# USB_to_UART.net
KiCad netlist of a schematic drawn in Altium Designer
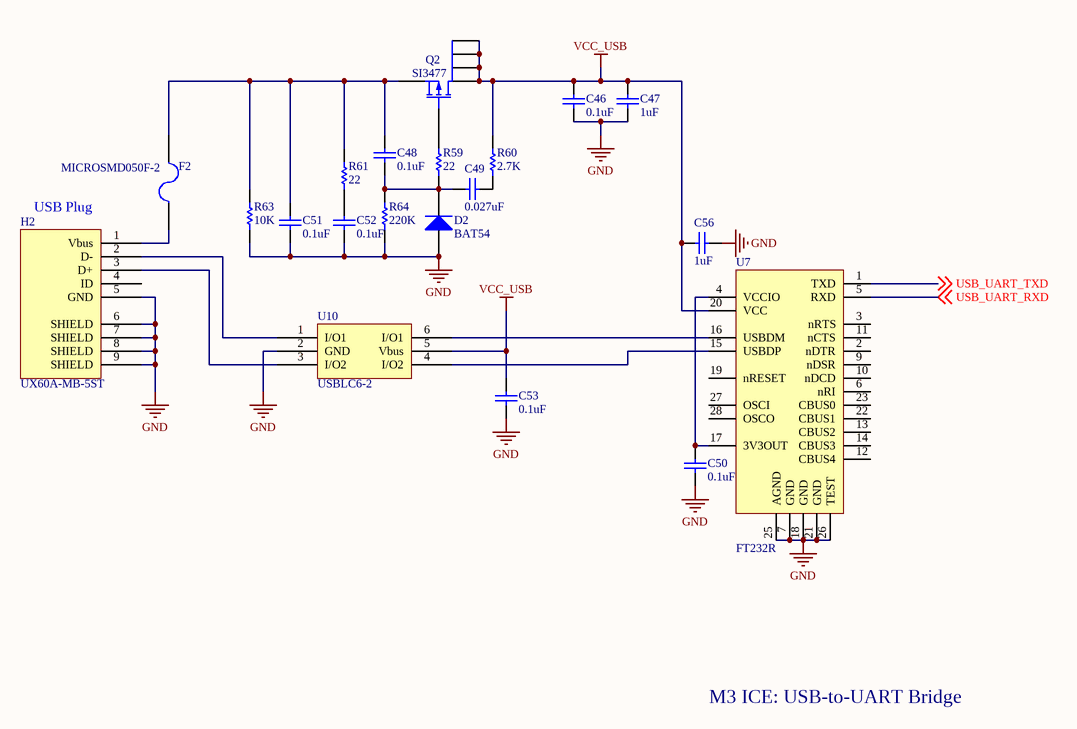
[diagram p0: USB_to_UART.SchDoc]

(export (version "E")
  (design (tool "Eeschema 10.0.6"))
  (components
    (comp (ref "C46")
      (value "0.1uF")
      (footprint "1608[0603]")
      (description "Capacitor (Semiconductor SIM Model)")
      (fields
        (field (name "DISTPARTNO") "1276-1005-1-ND")
        (field (name "MANPARTNO") "CL10B104KO8NNNC")
        (field (name "PUBLISHER") "Altium Limited")
      )
      (libsource (lib "Miscellaneous Devices") (part "Cap Semi"))
    )
    (comp (ref "C47")
      (value "1uF")
      (footprint "1608[0603]")
      (description "Capacitor (Semiconductor SIM Model)")
      (fields
        (field (name "DISTPARTNO") "1276-1019-1-ND")
        (field (name "MANPARTNO") "CL10B105KO8NNNC")
        (field (name "PUBLISHER") "Altium Limited")
      )
      (libsource (lib "Miscellaneous Devices") (part "Cap Semi"))
    )
    (comp (ref "C48")
      (value "0.1uF")
      (footprint "1608[0603]")
      (description "Capacitor (Semiconductor SIM Model)")
      (fields
        (field (name "DISTPARTNO") "1276-1005-1-ND")
        (field (name "MANPARTNO") "CL10B104KO8NNNC")
        (field (name "PUBLISHER") "Altium Limited")
      )
      (libsource (lib "Miscellaneous Devices") (part "Cap Semi"))
    )
    (comp (ref "C49")
      (value "0.027uF")
      (footprint "1608[0603]")
      (description "Capacitor (Semiconductor SIM Model)")
      (fields
        (field (name "DISTPARTNO") "478-1232-1-ND")
        (field (name "MANPARTNO") "06035C273KAT2A")
        (field (name "PUBLISHER") "Altium Limited")
      )
      (libsource (lib "Miscellaneous Devices") (part "Cap Semi"))
    )
    (comp (ref "C50")
      (value "0.1uF")
      (footprint "1608[0603]")
      (description "Capacitor (Semiconductor SIM Model)")
      (fields
        (field (name "DISTPARTNO") "1276-1005-1-ND")
        (field (name "MANPARTNO") "CL10B104KO8NNNC")
        (field (name "PUBLISHER") "Altium Limited")
      )
      (libsource (lib "Miscellaneous Devices") (part "Cap Semi"))
    )
    (comp (ref "C51")
      (value "0.1uF")
      (footprint "1608[0603]")
      (description "Capacitor (Semiconductor SIM Model)")
      (fields
        (field (name "DISTPARTNO") "1276-1005-1-ND")
        (field (name "MANPARTNO") "CL10B104KO8NNNC")
        (field (name "PUBLISHER") "Altium Limited")
      )
      (libsource (lib "Miscellaneous Devices") (part "Cap Semi"))
    )
    (comp (ref "C52")
      (value "0.1uF")
      (footprint "1608[0603]")
      (description "Capacitor (Semiconductor SIM Model)")
      (fields
        (field (name "DISTPARTNO") "1276-1005-1-ND")
        (field (name "MANPARTNO") "CL10B104KO8NNNC")
        (field (name "PUBLISHER") "Altium Limited")
      )
      (libsource (lib "Miscellaneous Devices") (part "Cap Semi"))
    )
    (comp (ref "C53")
      (value "0.1uF")
      (footprint "1608[0603]")
      (description "Capacitor (Semiconductor SIM Model)")
      (fields
        (field (name "DISTPARTNO") "1276-1005-1-ND")
        (field (name "MANPARTNO") "CL10B104KO8NNNC")
        (field (name "PUBLISHER") "Altium Limited")
      )
      (libsource (lib "Miscellaneous Devices") (part "Cap Semi"))
    )
    (comp (ref "C56")
      (value "1uF")
      (footprint "1608[0603]")
      (description "Capacitor (Semiconductor SIM Model)")
      (fields
        (field (name "DISTPARTNO") "1276-1019-1-ND")
        (field (name "MANPARTNO") "CL10B105KO8NNNC")
        (field (name "PUBLISHER") "Altium Limited")
      )
      (libsource (lib "Miscellaneous Devices") (part "Cap Semi"))
    )
    (comp (ref "D2")
      (value "BAT54")
      (footprint "SOT-23_N")
      (description "Low-Loss RF Switching Diode")
      (fields
        (field (name "DISTPARTNO") "BAT54-FDICT-ND")
        (field (name "MANPARTNO") "BAT54-7-F")
        (field (name "PUBLISHER") "Altium Limited")
      )
      (libsource (lib "Miscellaneous Devices") (part "Diode BAT18"))
    )
    (comp (ref "F2")
      (value "MICROSMD050F-2")
      (footprint "1210")
      (description "POLYSWITCH 0.50A RESET FUSE SMD")
      (fields (field (name "DISTPARTNO") "MICROSMD050FCT-ND"))
      (libsource (lib "M3") (part "Fuse MICROSMD050F-2"))
    )
    (comp (ref "H2")
      (value "UX60A-MB-5ST")
      (footprint "USB Mini-B")
      (description "USB mini-B")
      (fields (field (name "DISTPARTNO") "H2961CT-ND"))
      (libsource (lib "M3") (part "UX60-MB-5ST"))
    )
    (comp (ref "Q2")
      (value "SI3477")
      (footprint "TSOP-6")
      (description "P-Channel MOSFET")
      (fields (field (name "DISTPARTNO") "SI3477DV-T1-GE3CT-ND") (field (name "MANPARTNO") "SI3477DV-T1-GE3"))
      (libsource (lib "M3") (part "SI3477"))
    )
    (comp (ref "R59")
      (value "22")
      (footprint "0603")
      (description "Semiconductor Resistor")
      (fields
        (field (name "DISTPARTNO") "P22GCT-ND")
        (field (name "MANPARTNO") "ERJ-3GEYJ220V")
        (field (name "PUBLISHER") "Altium Limited")
      )
      (libsource (lib "M3") (part "Res Chip"))
    )
    (comp (ref "R60")
      (value "2.7K")
      (footprint "0603")
      (description "Semiconductor Resistor")
      (fields
        (field (name "DISTPARTNO") "P2.7KGCT-ND")
        (field (name "MANPARTNO") "ERJ-3GEYJ272V")
        (field (name "PUBLISHER") "Altium Limited")
      )
      (libsource (lib "M3") (part "Res Chip"))
    )
    (comp (ref "R61")
      (value "22")
      (footprint "0603")
      (description "Semiconductor Resistor")
      (fields
        (field (name "DISTPARTNO") "P22GCT-ND")
        (field (name "MANPARTNO") "ERJ-3GEYJ220V")
        (field (name "PUBLISHER") "Altium Limited")
      )
      (libsource (lib "M3") (part "Res Chip"))
    )
    (comp (ref "R63")
      (value "10K")
      (footprint "0603")
      (description "Semiconductor Resistor")
      (fields
        (field (name "DISTPARTNO") "P10KGCT-ND")
        (field (name "MANPARTNO") "ERJ-3GEYJ103V")
        (field (name "PUBLISHER") "Altium Limited")
      )
      (libsource (lib "M3") (part "Res Chip"))
    )
    (comp (ref "R64")
      (value "220K")
      (footprint "0603")
      (description "Semiconductor Resistor")
      (fields
        (field (name "DISTPARTNO") "P220KGCT-ND")
        (field (name "MANPARTNO") "ERJ-3GEYJ224V")
        (field (name "PUBLISHER") "Altium Limited")
      )
      (libsource (lib "M3") (part "Res Chip"))
    )
    (comp (ref "U7")
      (value "FT232R")
      (footprint "SSOP20")
      (fields (field (name "DISTPARTNO") "768-1007-1-ND") (field (name "MANPARTNO") "FT232RL-REEL"))
      (libsource (lib "uwb-library") (part "FT232R"))
    )
    (comp (ref "U10")
      (value "USBLC6-2")
      (footprint "SOT23-6_L")
      (description "USB ESD Protection")
      (fields (field (name "DISTPARTNO") "497-11882-1-ND") (field (name "MANPARTNO") "USBLC6-2SC6Y"))
      (libsource (lib "M3") (part "USBLC6-2"))
    )
  )
  (nets
    (net (code "1") (name "GND") (class "Default")
      (node (ref "C46") (pin "1") (pinfunction "1_1") (pintype "passive"))
      (node (ref "C47") (pin "1") (pinfunction "1_1") (pintype "passive"))
      (node (ref "C50") (pin "1") (pinfunction "1_1") (pintype "passive"))
      (node (ref "C51") (pin "1") (pinfunction "1_1") (pintype "passive"))
      (node (ref "C52") (pin "1") (pinfunction "1_1") (pintype "passive"))
      (node (ref "C53") (pin "1") (pinfunction "1_1") (pintype "passive"))
      (node (ref "C56") (pin "1") (pinfunction "1_1") (pintype "passive"))
      (node (ref "D2") (pin "1") (pinfunction "A_1") (pintype "passive"))
      (node (ref "H2") (pin "5") (pinfunction "GND_5") (pintype "passive"))
      (node (ref "H2") (pin "6") (pinfunction "SHIELD_6") (pintype "passive"))
      (node (ref "H2") (pin "7") (pinfunction "SHIELD_7") (pintype "passive"))
      (node (ref "H2") (pin "8") (pinfunction "SHIELD_8") (pintype "passive"))
      (node (ref "H2") (pin "9") (pinfunction "SHIELD_9") (pintype "passive"))
      (node (ref "R63") (pin "1") (pinfunction "1_1") (pintype "passive"))
      (node (ref "R64") (pin "1") (pinfunction "1_1") (pintype "passive"))
      (node (ref "U10") (pin "2") (pinfunction "GND_2") (pintype "passive"))
      (node (ref "U7") (pin "18") (pinfunction "GND_18") (pintype "passive"))
      (node (ref "U7") (pin "21") (pinfunction "GND_21") (pintype "passive"))
      (node (ref "U7") (pin "25") (pinfunction "AGND_25") (pintype "passive"))
      (node (ref "U7") (pin "26") (pinfunction "TEST_26") (pintype "passive"))
      (node (ref "U7") (pin "7") (pinfunction "GND_7") (pintype "passive"))
    )
    (net (code "2") (name "Net-(C49-Pad1)") (class "Default")
      (node (ref "C49") (pin "1") (pinfunction "1_1") (pintype "passive"))
      (node (ref "R60") (pin "1") (pinfunction "1_1") (pintype "passive"))
    )
    (net (code "3") (name "Net-(C52-Pad2)") (class "Default")
      (node (ref "C52") (pin "2") (pinfunction "2_2") (pintype "passive"))
      (node (ref "R61") (pin "1") (pinfunction "1_1") (pintype "passive"))
    )
    (net (code "4") (name "Net-(D2-K)") (class "Default")
      (node (ref "C48") (pin "1") (pinfunction "1_1") (pintype "passive"))
      (node (ref "C49") (pin "2") (pinfunction "2_2") (pintype "passive"))
      (node (ref "D2") (pin "3") (pinfunction "K_3") (pintype "passive"))
      (node (ref "R59") (pin "1") (pinfunction "1_1") (pintype "passive"))
      (node (ref "R64") (pin "2") (pinfunction "2_2") (pintype "passive"))
    )
    (net (code "5") (name "Net-(H2-D+)") (class "Default")
      (node (ref "H2") (pin "3") (pinfunction "D+_3") (pintype "passive"))
      (node (ref "U10") (pin "3") (pinfunction "I/O2_3") (pintype "passive"))
    )
    (net (code "6") (name "Net-(H2-D-)") (class "Default")
      (node (ref "H2") (pin "2") (pinfunction "D-_2") (pintype "passive"))
      (node (ref "U10") (pin "1") (pinfunction "I/O1_1") (pintype "passive"))
    )
    (net (code "7") (name "Net-(H2-Vbus)") (class "Default")
      (node (ref "F2") (pin "1") (pinfunction "1_1") (pintype "passive"))
      (node (ref "H2") (pin "1") (pinfunction "Vbus_1") (pintype "passive"))
    )
    (net (code "8") (name "Net-(Q2-G)") (class "Default")
      (node (ref "Q2") (pin "3") (pinfunction "G_3") (pintype "passive"))
      (node (ref "R59") (pin "2") (pinfunction "2_2") (pintype "passive"))
    )
    (net (code "9") (name "Net-(Q2-S)") (class "Default")
      (node (ref "C48") (pin "2") (pinfunction "2_2") (pintype "passive"))
      (node (ref "C51") (pin "2") (pinfunction "2_2") (pintype "passive"))
      (node (ref "F2") (pin "2") (pinfunction "2_2") (pintype "passive"))
      (node (ref "Q2") (pin "4") (pinfunction "S_4") (pintype "passive"))
      (node (ref "R61") (pin "2") (pinfunction "2_2") (pintype "passive"))
      (node (ref "R63") (pin "2") (pinfunction "2_2") (pintype "passive"))
    )
    (net (code "10") (name "Net-(U7-3V3OUT)") (class "Default")
      (node (ref "C50") (pin "2") (pinfunction "2_2") (pintype "passive"))
      (node (ref "U7") (pin "17") (pinfunction "3V3OUT_17") (pintype "passive"))
      (node (ref "U7") (pin "4") (pinfunction "VCCIO_4") (pintype "passive"))
    )
    (net (code "11") (name "Net-(U7-USBDM)") (class "Default")
      (node (ref "U10") (pin "6") (pinfunction "I/O1_6") (pintype "passive"))
      (node (ref "U7") (pin "16") (pinfunction "USBDM_16") (pintype "passive"))
    )
    (net (code "12") (name "Net-(U7-USBDP)") (class "Default")
      (node (ref "U10") (pin "4") (pinfunction "I/O2_4") (pintype "passive"))
      (node (ref "U7") (pin "15") (pinfunction "USBDP_15") (pintype "passive"))
    )
    (net (code "13") (name "USB_UART_RXD") (class "Default")
      (node (ref "U7") (pin "5") (pinfunction "RXD_5") (pintype "passive"))
    )
    (net (code "14") (name "USB_UART_TXD") (class "Default")
      (node (ref "U7") (pin "1") (pinfunction "TXD_1") (pintype "passive"))
    )
    (net (code "15") (name "VCC_USB") (class "Default")
      (node (ref "C46") (pin "2") (pinfunction "2_2") (pintype "passive"))
      (node (ref "C47") (pin "2") (pinfunction "2_2") (pintype "passive"))
      (node (ref "C53") (pin "2") (pinfunction "2_2") (pintype "passive"))
      (node (ref "C56") (pin "2") (pinfunction "2_2") (pintype "passive"))
      (node (ref "Q2") (pin "1") (pinfunction "D_1") (pintype "passive"))
      (node (ref "Q2") (pin "2") (pinfunction "D_2") (pintype "passive"))
      (node (ref "Q2") (pin "5") (pinfunction "D_5") (pintype "passive"))
      (node (ref "Q2") (pin "6") (pinfunction "D_6") (pintype "passive"))
      (node (ref "R60") (pin "2") (pinfunction "2_2") (pintype "passive"))
      (node (ref "U10") (pin "5") (pinfunction "Vbus_5") (pintype "passive"))
      (node (ref "U7") (pin "20") (pinfunction "VCC_20") (pintype "passive"))
    )
    (net (code "16") (name "unconnected-(H2-ID-Pad4)") (class "Default")
      (node (ref "H2") (pin "4") (pinfunction "ID_4") (pintype "passive"))
    )
    (net (code "17") (name "unconnected-(U7-CBUS0-Pad23)") (class "Default")
      (node (ref "U7") (pin "23") (pinfunction "CBUS0_23") (pintype "passive"))
    )
    (net (code "18") (name "unconnected-(U7-CBUS1-Pad22)") (class "Default")
      (node (ref "U7") (pin "22") (pinfunction "CBUS1_22") (pintype "passive"))
    )
    (net (code "19") (name "unconnected-(U7-CBUS2-Pad13)") (class "Default")
      (node (ref "U7") (pin "13") (pinfunction "CBUS2_13") (pintype "passive"))
    )
    (net (code "20") (name "unconnected-(U7-CBUS3-Pad14)") (class "Default")
      (node (ref "U7") (pin "14") (pinfunction "CBUS3_14") (pintype "passive"))
    )
    (net (code "21") (name "unconnected-(U7-CBUS4-Pad12)") (class "Default")
      (node (ref "U7") (pin "12") (pinfunction "CBUS4_12") (pintype "passive"))
    )
    (net (code "22") (name "unconnected-(U7-OSCI-Pad27)") (class "Default")
      (node (ref "U7") (pin "27") (pinfunction "OSCI_27") (pintype "passive"))
    )
    (net (code "23") (name "unconnected-(U7-OSCO-Pad28)") (class "Default")
      (node (ref "U7") (pin "28") (pinfunction "OSCO_28") (pintype "passive"))
    )
    (net (code "24") (name "unconnected-(U7-nCTS-Pad11)") (class "Default")
      (node (ref "U7") (pin "11") (pinfunction "nCTS_11") (pintype "passive"))
    )
    (net (code "25") (name "unconnected-(U7-nDCD-Pad10)") (class "Default")
      (node (ref "U7") (pin "10") (pinfunction "nDCD_10") (pintype "passive"))
    )
    (net (code "26") (name "unconnected-(U7-nDSR-Pad9)") (class "Default")
      (node (ref "U7") (pin "9") (pinfunction "nDSR_9") (pintype "passive"))
    )
    (net (code "27") (name "unconnected-(U7-nDTR-Pad2)") (class "Default")
      (node (ref "U7") (pin "2") (pinfunction "nDTR_2") (pintype "passive"))
    )
    (net (code "28") (name "unconnected-(U7-nRESET-Pad19)") (class "Default")
      (node (ref "U7") (pin "19") (pinfunction "nRESET_19") (pintype "passive"))
    )
    (net (code "29") (name "unconnected-(U7-nRI-Pad6)") (class "Default")
      (node (ref "U7") (pin "6") (pinfunction "nRI_6") (pintype "passive"))
    )
    (net (code "30") (name "unconnected-(U7-nRTS-Pad3)") (class "Default")
      (node (ref "U7") (pin "3") (pinfunction "nRTS_3") (pintype "passive"))
    )
  )
)
